# -50vrailtorailwithBoost.net
KiCad netlist of a schematic drawn in EAGLE
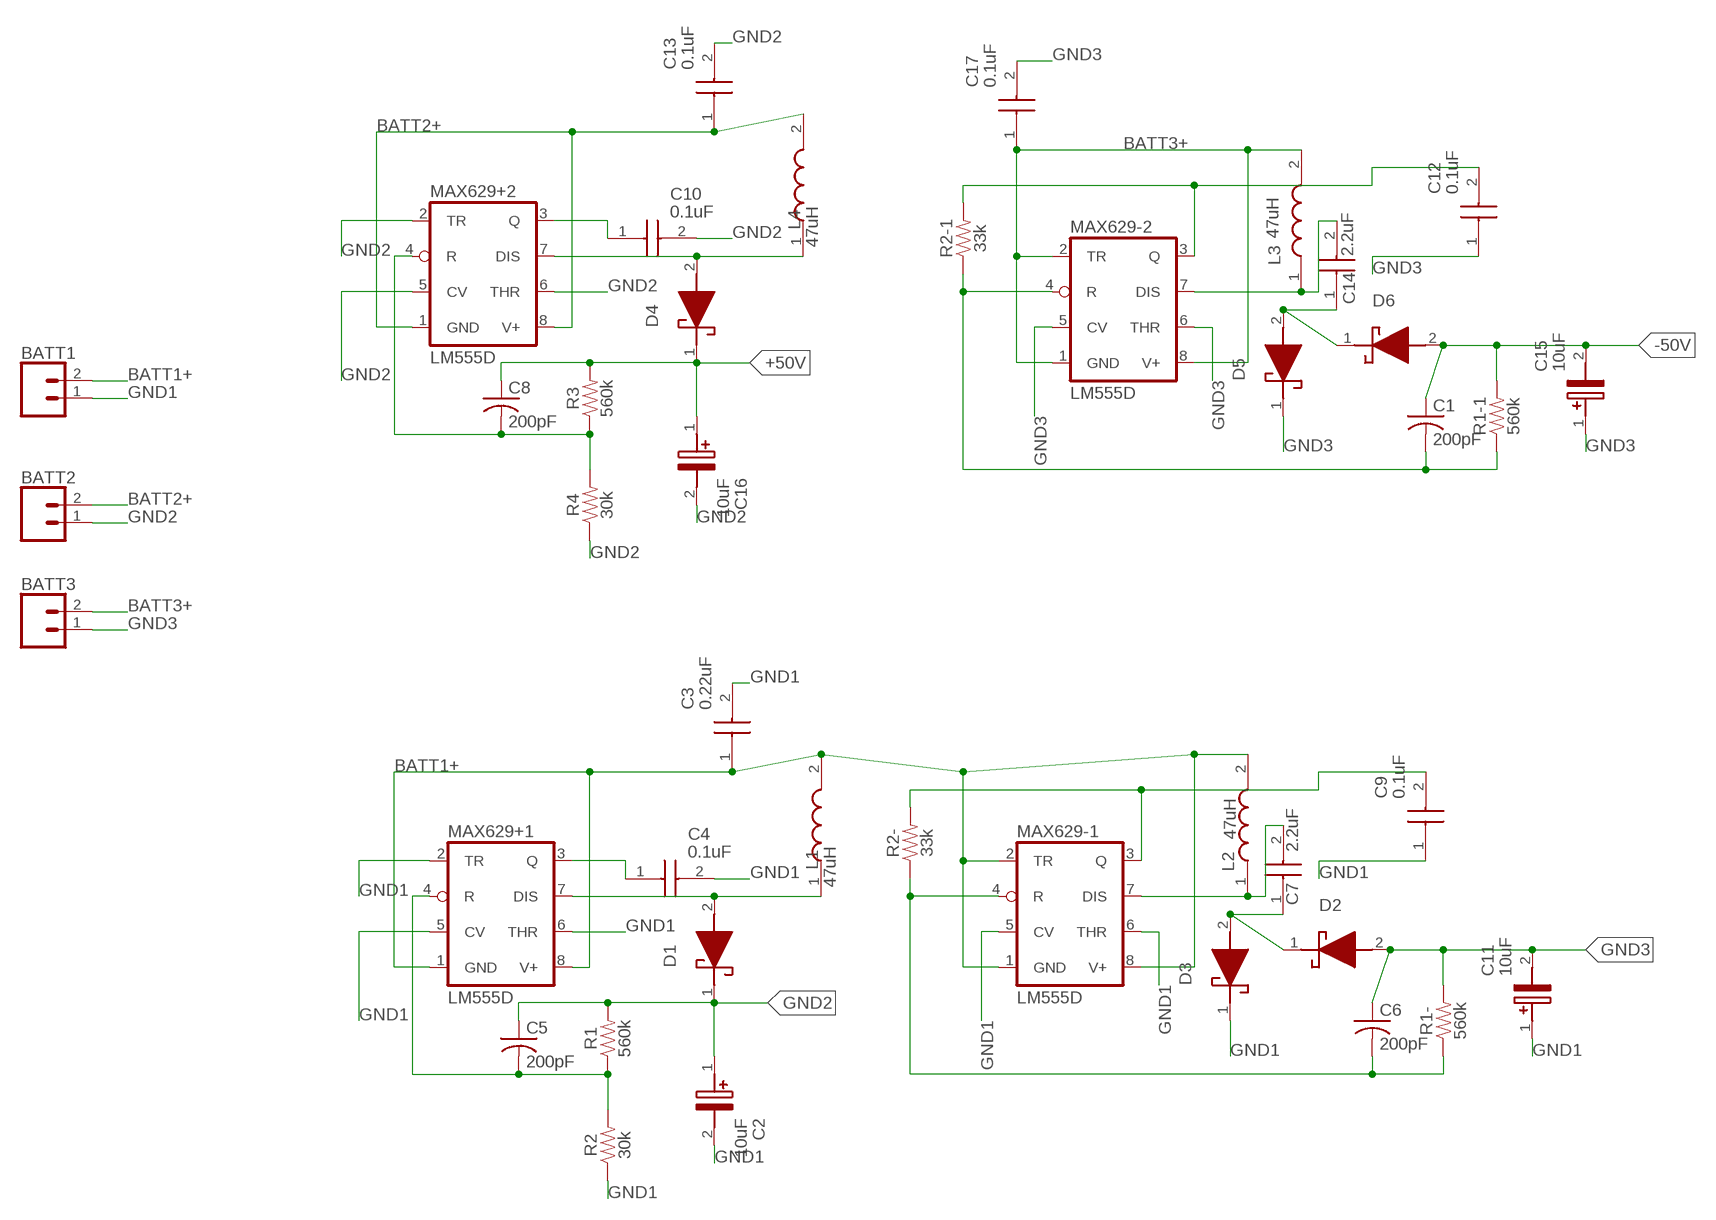
[diagram p0: schematic, sheet 1]

(export (version "E")
  (design (tool "Eeschema 10.0.6"))
  (components
    (comp (ref "BATT1")
      (value "CONN_02")
      (footprint "eagle-import:1X02")
      (libsource (lib "eagle-import") (part "CONN_02"))
    )
    (comp (ref "BATT2")
      (value "CONN_02")
      (footprint "eagle-import:1X02")
      (libsource (lib "eagle-import") (part "CONN_02"))
    )
    (comp (ref "BATT3")
      (value "CONN_02")
      (footprint "eagle-import:1X02")
      (libsource (lib "eagle-import") (part "CONN_02"))
    )
    (comp (ref "C1")
      (value "200pF")
      (footprint "eagle-import:C1206")
      (libsource (lib "eagle-import") (part "C-USC1206"))
    )
    (comp (ref "C2")
      (value "10uF")
      (footprint "eagle-import:EEE1AA220WR")
      (fields
        (field (name "MANUFACTURER_PART_NUMBER") "EEE-FN1H100UR")
        (field (name "MOUSER_PART_NUMBER") "667-EEE-FN1H100UR")
      )
      (libsource (lib "eagle-import") (part "EEE-FN1H100UR"))
    )
    (comp (ref "C3")
      (value "0.22uF")
      (footprint "eagle-import:C1206")
      (fields
        (field (name "MANUFACTURER_PART_NUMBER") "C1206C224J1RACAUTO")
        (field (name "MOUSER_PART_NUMBER") "80-C1206C224J1RAUTO")
      )
      (libsource (lib "eagle-import") (part "C1206C224J1RACAUTO"))
    )
    (comp (ref "C4")
      (value "0.1uF")
      (footprint "eagle-import:CAPC3316X195N")
      (fields
        (field (name "MANUFACTURER_PART_NUMBER") "C1206X222KGRACAUTO")
        (field (name "MOUSER_PART_NUMBER") "80-C1206X222KGRAUTO")
      )
      (libsource (lib "eagle-import") (part "C1206X222KGRACAUTO"))
    )
    (comp (ref "C5")
      (value "200pF")
      (footprint "eagle-import:C1206")
      (libsource (lib "eagle-import") (part "C-USC1206"))
    )
    (comp (ref "C6")
      (value "200pF")
      (footprint "eagle-import:C1206")
      (libsource (lib "eagle-import") (part "C-USC1206"))
    )
    (comp (ref "C7")
      (value "2.2uF")
      (footprint "eagle-import:CAPC2012X152N")
      (fields
        (field (name "MANUFACTURER_PART_NUMBER") "08055C225KAT2A")
        (field (name "MOUSER_PART_NUMBER") "581-08055C225KAT2A")
      )
      (libsource (lib "eagle-import") (part "08055C225KAT2A"))
    )
    (comp (ref "C8")
      (value "200pF")
      (footprint "eagle-import:C1206")
      (libsource (lib "eagle-import") (part "C-USC1206"))
    )
    (comp (ref "C9")
      (value "0.1uF")
      (footprint "eagle-import:CAPC3316X195N")
      (fields
        (field (name "MANUFACTURER_PART_NUMBER") "C1206X222KGRACAUTO")
        (field (name "MOUSER_PART_NUMBER") "80-C1206X222KGRAUTO")
      )
      (libsource (lib "eagle-import") (part "C1206X222KGRACAUTO"))
    )
    (comp (ref "C10")
      (value "0.1uF")
      (footprint "eagle-import:CAPC3316X195N")
      (fields
        (field (name "MANUFACTURER_PART_NUMBER") "C1206X222KGRACAUTO")
        (field (name "MOUSER_PART_NUMBER") "80-C1206X222KGRAUTO")
      )
      (libsource (lib "eagle-import") (part "C1206X222KGRACAUTO"))
    )
    (comp (ref "C11")
      (value "10uF")
      (footprint "eagle-import:EEE1AA220WR")
      (fields
        (field (name "MANUFACTURER_PART_NUMBER") "EEE-FN1H100UR")
        (field (name "MOUSER_PART_NUMBER") "667-EEE-FN1H100UR")
      )
      (libsource (lib "eagle-import") (part "EEE-FN1H100UR"))
    )
    (comp (ref "C12")
      (value "0.1uF")
      (footprint "eagle-import:CAPC3316X195N")
      (fields
        (field (name "MANUFACTURER_PART_NUMBER") "C1206X222KGRACAUTO")
        (field (name "MOUSER_PART_NUMBER") "80-C1206X222KGRAUTO")
      )
      (libsource (lib "eagle-import") (part "C1206X222KGRACAUTO"))
    )
    (comp (ref "C13")
      (value "0.1uF")
      (footprint "eagle-import:C1206")
      (fields
        (field (name "MANUFACTURER_PART_NUMBER") "C1206C224J1RACAUTO")
        (field (name "MOUSER_PART_NUMBER") "80-C1206C224J1RAUTO")
      )
      (libsource (lib "eagle-import") (part "C1206C224J1RACAUTO"))
    )
    (comp (ref "C14")
      (value "2.2uF")
      (footprint "eagle-import:CAPC2012X152N")
      (fields
        (field (name "MANUFACTURER_PART_NUMBER") "08055C225KAT2A")
        (field (name "MOUSER_PART_NUMBER") "581-08055C225KAT2A")
      )
      (libsource (lib "eagle-import") (part "08055C225KAT2A"))
    )
    (comp (ref "C15")
      (value "10uF")
      (footprint "eagle-import:EEE1AA220WR")
      (fields
        (field (name "MANUFACTURER_PART_NUMBER") "EEE-FN1H100UR")
        (field (name "MOUSER_PART_NUMBER") "667-EEE-FN1H100UR")
      )
      (libsource (lib "eagle-import") (part "EEE-FN1H100UR"))
    )
    (comp (ref "C16")
      (value "10uF")
      (footprint "eagle-import:EEE1AA220WR")
      (fields
        (field (name "MANUFACTURER_PART_NUMBER") "EEE-FN1H100UR")
        (field (name "MOUSER_PART_NUMBER") "667-EEE-FN1H100UR")
      )
      (libsource (lib "eagle-import") (part "EEE-FN1H100UR"))
    )
    (comp (ref "C17")
      (value "0.1uF")
      (footprint "eagle-import:C1206")
      (fields
        (field (name "MANUFACTURER_PART_NUMBER") "C1206C224J1RACAUTO")
        (field (name "MOUSER_PART_NUMBER") "80-C1206C224J1RAUTO")
      )
      (libsource (lib "eagle-import") (part "C1206C224J1RACAUTO"))
    )
    (comp (ref "D1")
      (value "1N5819HW-7")
      (footprint "eagle-import:SOD3716X135N")
      (fields (field (name "MOUSER_PART_NUMBER") "621-1N5819HW"))
      (libsource (lib "eagle-import") (part "1N5819HW-7"))
    )
    (comp (ref "D2")
      (value "1N5819HW-7")
      (footprint "eagle-import:SOD3716X135N")
      (fields (field (name "MOUSER_PART_NUMBER") "621-1N5819HW"))
      (libsource (lib "eagle-import") (part "1N5819HW-7"))
    )
    (comp (ref "D3")
      (value "1N5819HW-7")
      (footprint "eagle-import:SOD3716X135N")
      (fields (field (name "MOUSER_PART_NUMBER") "621-1N5819HW"))
      (libsource (lib "eagle-import") (part "1N5819HW-7"))
    )
    (comp (ref "D4")
      (value "1N5819HW-7")
      (footprint "eagle-import:SOD3716X135N")
      (fields (field (name "MOUSER_PART_NUMBER") "621-1N5819HW"))
      (libsource (lib "eagle-import") (part "1N5819HW-7"))
    )
    (comp (ref "D5")
      (value "1N5819HW-7")
      (footprint "eagle-import:SOD3716X135N")
      (fields (field (name "MOUSER_PART_NUMBER") "621-1N5819HW"))
      (libsource (lib "eagle-import") (part "1N5819HW-7"))
    )
    (comp (ref "D6")
      (value "1N5819HW-7")
      (footprint "eagle-import:SOD3716X135N")
      (fields (field (name "MOUSER_PART_NUMBER") "621-1N5819HW"))
      (libsource (lib "eagle-import") (part "1N5819HW-7"))
    )
    (comp (ref "L1")
      (value "47uH")
      (footprint "eagle-import:SLF10145")
      (fields
        (field (name "MANUFACTURER_PART_NUMBER") "SLF10145T-470M1R4-PF")
        (field (name "MOUSER_PART_NUMBER") "810-SLF10145T-470M")
      )
      (libsource (lib "eagle-import") (part "SLF10145T-470M1R4-PF"))
    )
    (comp (ref "L2")
      (value "47uH")
      (footprint "eagle-import:SLF10145")
      (fields
        (field (name "MANUFACTURER_PART_NUMBER") "SLF10145T-470M1R4-PF")
        (field (name "MOUSER_PART_NUMBER") "810-SLF10145T-470M")
      )
      (libsource (lib "eagle-import") (part "SLF10145T-470M1R4-PF"))
    )
    (comp (ref "L3")
      (value "47uH")
      (footprint "eagle-import:SLF10145")
      (fields
        (field (name "MANUFACTURER_PART_NUMBER") "SLF10145T-470M1R4-PF")
        (field (name "MOUSER_PART_NUMBER") "810-SLF10145T-470M")
      )
      (libsource (lib "eagle-import") (part "SLF10145T-470M1R4-PF"))
    )
    (comp (ref "L4")
      (value "47uH")
      (footprint "eagle-import:SLF10145")
      (fields
        (field (name "MANUFACTURER_PART_NUMBER") "SLF10145T-470M1R4-PF")
        (field (name "MOUSER_PART_NUMBER") "810-SLF10145T-470M")
      )
      (libsource (lib "eagle-import") (part "SLF10145T-470M1R4-PF"))
    )
    (comp (ref "MAX629+1")
      (value "LM555D")
      (footprint "eagle-import:SO08")
      (libsource (lib "eagle-import") (part "555DLM"))
    )
    (comp (ref "MAX629+2")
      (value "LM555D")
      (footprint "eagle-import:SO08")
      (libsource (lib "eagle-import") (part "555DLM"))
    )
    (comp (ref "MAX629-1")
      (value "LM555D")
      (footprint "eagle-import:SO08")
      (libsource (lib "eagle-import") (part "555DLM"))
    )
    (comp (ref "MAX629-2")
      (value "LM555D")
      (footprint "eagle-import:SO08")
      (libsource (lib "eagle-import") (part "555DLM"))
    )
    (comp (ref "R1")
      (value "560k")
      (footprint "eagle-import:0805")
      (libsource (lib "eagle-import") (part "0.3OHM-0805-1/8W-1%"))
    )
    (comp (ref "R1-")
      (value "560k")
      (footprint "eagle-import:0805")
      (libsource (lib "eagle-import") (part "0.3OHM-0805-1/8W-1%"))
    )
    (comp (ref "R1-1")
      (value "560k")
      (footprint "eagle-import:0805")
      (libsource (lib "eagle-import") (part "0.3OHM-0805-1/8W-1%"))
    )
    (comp (ref "R2")
      (value "30k")
      (footprint "eagle-import:0805")
      (libsource (lib "eagle-import") (part "0.3OHM-0805-1/8W-1%"))
    )
    (comp (ref "R2-")
      (value "33k")
      (footprint "eagle-import:0805")
      (libsource (lib "eagle-import") (part "0.3OHM-0805-1/8W-1%"))
    )
    (comp (ref "R2-1")
      (value "33k")
      (footprint "eagle-import:0805")
      (libsource (lib "eagle-import") (part "0.3OHM-0805-1/8W-1%"))
    )
    (comp (ref "R3")
      (value "560k")
      (footprint "eagle-import:0805")
      (libsource (lib "eagle-import") (part "0.3OHM-0805-1/8W-1%"))
    )
    (comp (ref "R4")
      (value "30k")
      (footprint "eagle-import:0805")
      (libsource (lib "eagle-import") (part "0.3OHM-0805-1/8W-1%"))
    )
  )
  (nets
    (net (code "1") (name "+50V") (class "Default")
      (node (ref "C16") (pin "1") (pinfunction "+_1") (pintype "bidirectional"))
      (node (ref "C8") (pin "1") (pinfunction "1_1") (pintype "passive"))
      (node (ref "D4") (pin "1") (pinfunction "K_1") (pintype "bidirectional"))
      (node (ref "R3") (pin "2") (pinfunction "2_2") (pintype "passive"))
    )
    (net (code "2") (name "-50V") (class "Default")
      (node (ref "C1") (pin "1") (pinfunction "1_1") (pintype "passive"))
      (node (ref "C15") (pin "2") (pinfunction "-_2") (pintype "bidirectional"))
      (node (ref "D6") (pin "2") (pinfunction "A_2") (pintype "bidirectional"))
      (node (ref "R1-1") (pin "2") (pinfunction "2_2") (pintype "passive"))
    )
    (net (code "3") (name "/BATT1+") (class "Default")
      (node (ref "BATT1") (pin "2") (pinfunction "2_2") (pintype "passive"))
      (node (ref "C3") (pin "1") (pinfunction "1_1") (pintype "bidirectional"))
      (node (ref "L1") (pin "2") (pinfunction "2_2") (pintype "bidirectional"))
      (node (ref "L2") (pin "2") (pinfunction "2_2") (pintype "bidirectional"))
      (node (ref "MAX629+1") (pin "1") (pinfunction "GND_1") (pintype "power_in"))
      (node (ref "MAX629+1") (pin "8") (pinfunction "V+_8") (pintype "power_in"))
      (node (ref "MAX629-1") (pin "1") (pinfunction "GND_1") (pintype "power_in"))
      (node (ref "MAX629-1") (pin "2") (pinfunction "TR_2") (pintype "input"))
      (node (ref "MAX629-1") (pin "8") (pinfunction "V+_8") (pintype "power_in"))
    )
    (net (code "4") (name "/BATT2+") (class "Default")
      (node (ref "BATT2") (pin "2") (pinfunction "2_2") (pintype "passive"))
      (node (ref "C13") (pin "1") (pinfunction "1_1") (pintype "bidirectional"))
      (node (ref "L4") (pin "2") (pinfunction "2_2") (pintype "bidirectional"))
      (node (ref "MAX629+2") (pin "1") (pinfunction "GND_1") (pintype "power_in"))
      (node (ref "MAX629+2") (pin "8") (pinfunction "V+_8") (pintype "power_in"))
    )
    (net (code "5") (name "/BATT3+") (class "Default")
      (node (ref "BATT3") (pin "2") (pinfunction "2_2") (pintype "passive"))
      (node (ref "C17") (pin "1") (pinfunction "1_1") (pintype "bidirectional"))
      (node (ref "L3") (pin "2") (pinfunction "2_2") (pintype "bidirectional"))
      (node (ref "MAX629-2") (pin "1") (pinfunction "GND_1") (pintype "power_in"))
      (node (ref "MAX629-2") (pin "2") (pinfunction "TR_2") (pintype "input"))
      (node (ref "MAX629-2") (pin "8") (pinfunction "V+_8") (pintype "power_in"))
    )
    (net (code "6") (name "/GND1") (class "Default")
      (node (ref "BATT1") (pin "1") (pinfunction "1_1") (pintype "passive"))
      (node (ref "C11") (pin "1") (pinfunction "+_1") (pintype "bidirectional"))
      (node (ref "C2") (pin "2") (pinfunction "-_2") (pintype "bidirectional"))
      (node (ref "C3") (pin "2") (pinfunction "2_2") (pintype "bidirectional"))
      (node (ref "C4") (pin "2") (pinfunction "2_2") (pintype "bidirectional"))
      (node (ref "C9") (pin "1") (pinfunction "1_1") (pintype "bidirectional"))
      (node (ref "D3") (pin "1") (pinfunction "K_1") (pintype "bidirectional"))
      (node (ref "MAX629+1") (pin "2") (pinfunction "TR_2") (pintype "input"))
      (node (ref "MAX629+1") (pin "5") (pinfunction "CV_5") (pintype "input"))
      (node (ref "MAX629+1") (pin "6") (pinfunction "THR_6") (pintype "input"))
      (node (ref "MAX629-1") (pin "5") (pinfunction "CV_5") (pintype "input"))
      (node (ref "MAX629-1") (pin "6") (pinfunction "THR_6") (pintype "input"))
      (node (ref "R2") (pin "1") (pinfunction "1_1") (pintype "passive"))
    )
    (net (code "7") (name "GND2") (class "Default")
      (node (ref "BATT2") (pin "1") (pinfunction "1_1") (pintype "passive"))
      (node (ref "C10") (pin "2") (pinfunction "2_2") (pintype "bidirectional"))
      (node (ref "C13") (pin "2") (pinfunction "2_2") (pintype "bidirectional"))
      (node (ref "C16") (pin "2") (pinfunction "-_2") (pintype "bidirectional"))
      (node (ref "C2") (pin "1") (pinfunction "+_1") (pintype "bidirectional"))
      (node (ref "C5") (pin "1") (pinfunction "1_1") (pintype "passive"))
      (node (ref "D1") (pin "1") (pinfunction "K_1") (pintype "bidirectional"))
      (node (ref "MAX629+2") (pin "2") (pinfunction "TR_2") (pintype "input"))
      (node (ref "MAX629+2") (pin "5") (pinfunction "CV_5") (pintype "input"))
      (node (ref "MAX629+2") (pin "6") (pinfunction "THR_6") (pintype "input"))
      (node (ref "R1") (pin "2") (pinfunction "2_2") (pintype "passive"))
      (node (ref "R4") (pin "1") (pinfunction "1_1") (pintype "passive"))
    )
    (net (code "8") (name "GND3") (class "Default")
      (node (ref "BATT3") (pin "1") (pinfunction "1_1") (pintype "passive"))
      (node (ref "C11") (pin "2") (pinfunction "-_2") (pintype "bidirectional"))
      (node (ref "C12") (pin "1") (pinfunction "1_1") (pintype "bidirectional"))
      (node (ref "C15") (pin "1") (pinfunction "+_1") (pintype "bidirectional"))
      (node (ref "C17") (pin "2") (pinfunction "2_2") (pintype "bidirectional"))
      (node (ref "C6") (pin "1") (pinfunction "1_1") (pintype "passive"))
      (node (ref "D2") (pin "2") (pinfunction "A_2") (pintype "bidirectional"))
      (node (ref "D5") (pin "1") (pinfunction "K_1") (pintype "bidirectional"))
      (node (ref "MAX629-2") (pin "5") (pinfunction "CV_5") (pintype "input"))
      (node (ref "MAX629-2") (pin "6") (pinfunction "THR_6") (pintype "input"))
      (node (ref "R1-") (pin "2") (pinfunction "2_2") (pintype "passive"))
    )
    (net (code "9") (name "Net-(D1-A)") (class "Default")
      (node (ref "D1") (pin "2") (pinfunction "A_2") (pintype "bidirectional"))
      (node (ref "L1") (pin "1") (pinfunction "1_1") (pintype "bidirectional"))
      (node (ref "MAX629+1") (pin "7") (pinfunction "DIS_7") (pintype "input"))
    )
    (net (code "10") (name "Net-(D2-K)") (class "Default")
      (node (ref "C7") (pin "1") (pinfunction "1_1") (pintype "bidirectional"))
      (node (ref "D2") (pin "1") (pinfunction "K_1") (pintype "bidirectional"))
      (node (ref "D3") (pin "2") (pinfunction "A_2") (pintype "bidirectional"))
    )
    (net (code "11") (name "Net-(D4-A)") (class "Default")
      (node (ref "D4") (pin "2") (pinfunction "A_2") (pintype "bidirectional"))
      (node (ref "L4") (pin "1") (pinfunction "1_1") (pintype "bidirectional"))
      (node (ref "MAX629+2") (pin "7") (pinfunction "DIS_7") (pintype "input"))
    )
    (net (code "12") (name "Net-(D5-A)") (class "Default")
      (node (ref "C14") (pin "1") (pinfunction "1_1") (pintype "bidirectional"))
      (node (ref "D5") (pin "2") (pinfunction "A_2") (pintype "bidirectional"))
      (node (ref "D6") (pin "1") (pinfunction "K_1") (pintype "bidirectional"))
    )
    (net (code "13") (name "Net-(MAX629+1-Q)") (class "Default")
      (node (ref "C4") (pin "1") (pinfunction "1_1") (pintype "bidirectional"))
      (node (ref "MAX629+1") (pin "3") (pinfunction "Q_3") (pintype "output"))
    )
    (net (code "14") (name "Net-(MAX629+1-R)") (class "Default")
      (node (ref "C5") (pin "2") (pinfunction "2_2") (pintype "passive"))
      (node (ref "MAX629+1") (pin "4") (pinfunction "R_4") (pintype "input"))
      (node (ref "R1") (pin "1") (pinfunction "1_1") (pintype "passive"))
      (node (ref "R2") (pin "2") (pinfunction "2_2") (pintype "passive"))
    )
    (net (code "15") (name "Net-(MAX629+2-Q)") (class "Default")
      (node (ref "C10") (pin "1") (pinfunction "1_1") (pintype "bidirectional"))
      (node (ref "MAX629+2") (pin "3") (pinfunction "Q_3") (pintype "output"))
    )
    (net (code "16") (name "Net-(MAX629+2-R)") (class "Default")
      (node (ref "C8") (pin "2") (pinfunction "2_2") (pintype "passive"))
      (node (ref "MAX629+2") (pin "4") (pinfunction "R_4") (pintype "input"))
      (node (ref "R3") (pin "1") (pinfunction "1_1") (pintype "passive"))
      (node (ref "R4") (pin "2") (pinfunction "2_2") (pintype "passive"))
    )
    (net (code "17") (name "Net-(MAX629-1-DIS)") (class "Default")
      (node (ref "C7") (pin "2") (pinfunction "2_2") (pintype "bidirectional"))
      (node (ref "L2") (pin "1") (pinfunction "1_1") (pintype "bidirectional"))
      (node (ref "MAX629-1") (pin "7") (pinfunction "DIS_7") (pintype "input"))
    )
    (net (code "18") (name "Net-(MAX629-1-Q)") (class "Default")
      (node (ref "C9") (pin "2") (pinfunction "2_2") (pintype "bidirectional"))
      (node (ref "MAX629-1") (pin "3") (pinfunction "Q_3") (pintype "output"))
      (node (ref "R2-") (pin "2") (pinfunction "2_2") (pintype "passive"))
    )
    (net (code "19") (name "Net-(MAX629-1-R)") (class "Default")
      (node (ref "C6") (pin "2") (pinfunction "2_2") (pintype "passive"))
      (node (ref "MAX629-1") (pin "4") (pinfunction "R_4") (pintype "input"))
      (node (ref "R1-") (pin "1") (pinfunction "1_1") (pintype "passive"))
      (node (ref "R2-") (pin "1") (pinfunction "1_1") (pintype "passive"))
    )
    (net (code "20") (name "Net-(MAX629-2-DIS)") (class "Default")
      (node (ref "C14") (pin "2") (pinfunction "2_2") (pintype "bidirectional"))
      (node (ref "L3") (pin "1") (pinfunction "1_1") (pintype "bidirectional"))
      (node (ref "MAX629-2") (pin "7") (pinfunction "DIS_7") (pintype "input"))
    )
    (net (code "21") (name "Net-(MAX629-2-Q)") (class "Default")
      (node (ref "C12") (pin "2") (pinfunction "2_2") (pintype "bidirectional"))
      (node (ref "MAX629-2") (pin "3") (pinfunction "Q_3") (pintype "output"))
      (node (ref "R2-1") (pin "2") (pinfunction "2_2") (pintype "passive"))
    )
    (net (code "22") (name "Net-(MAX629-2-R)") (class "Default")
      (node (ref "C1") (pin "2") (pinfunction "2_2") (pintype "passive"))
      (node (ref "MAX629-2") (pin "4") (pinfunction "R_4") (pintype "input"))
      (node (ref "R1-1") (pin "1") (pinfunction "1_1") (pintype "passive"))
      (node (ref "R2-1") (pin "1") (pinfunction "1_1") (pintype "passive"))
    )
  )
)
